# SparkFun_Analog_MEMS_Microphone_Breakout.net
KiCad netlist of a schematic drawn in EAGLE
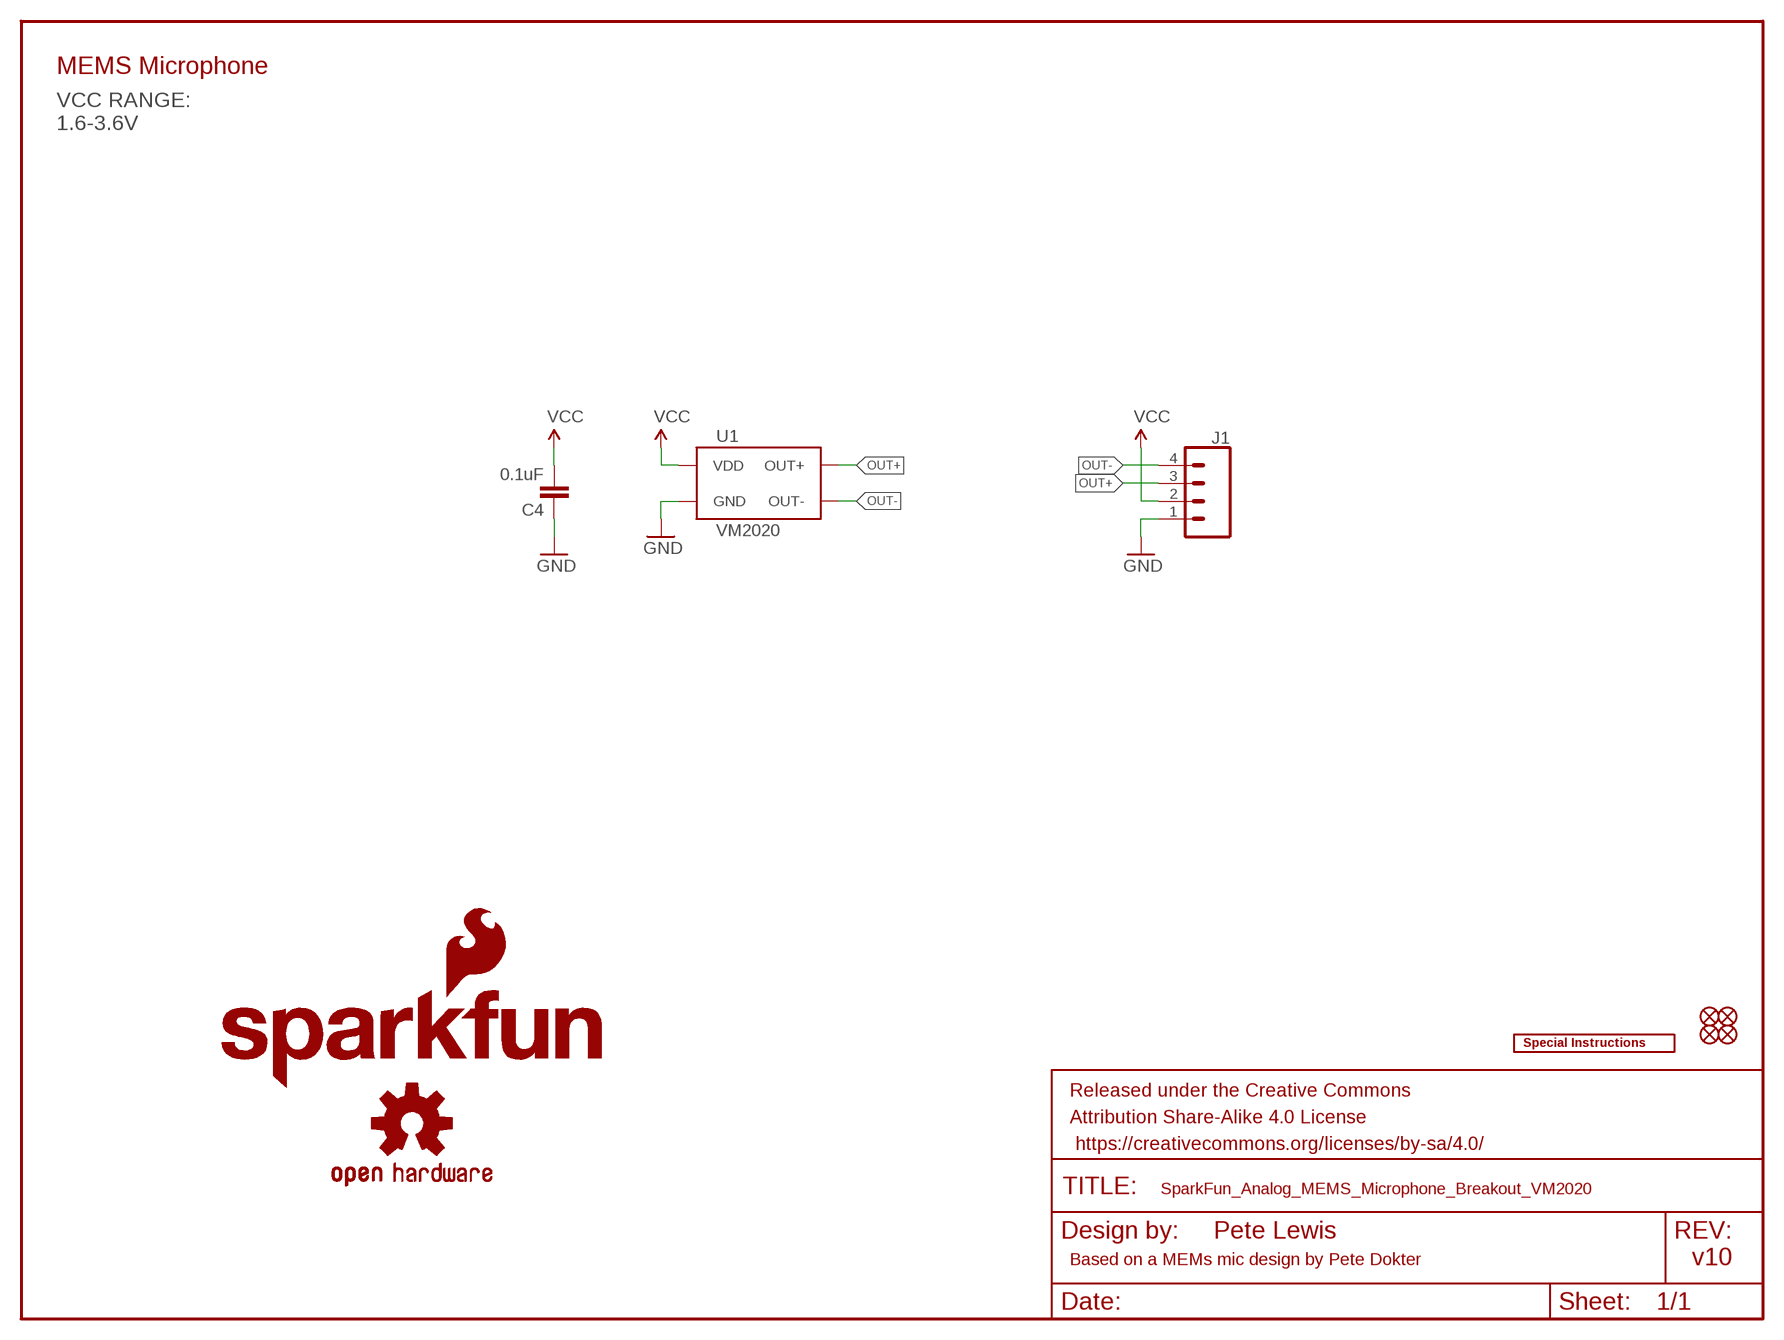
[diagram p0: schematic, sheet 1]

(export (version "E")
  (design (tool "Eeschema 10.0.6"))
  (components
    (comp (ref "C4")
      (value "0.1uF")
      (footprint "eagle-import:0603")
      (libsource (lib "eagle-import") (part "0.1UF-0603-25V-(+80/-20%)"))
    )
    (comp (ref "FD1")
      (value "FIDUCIALUFIDUCIAL")
      (footprint "eagle-import:FIDUCIAL-MICRO")
      (libsource (lib "eagle-import") (part "FIDUCIALUFIDUCIAL"))
    )
    (comp (ref "FD2")
      (value "FIDUCIALUFIDUCIAL")
      (footprint "eagle-import:FIDUCIAL-MICRO")
      (libsource (lib "eagle-import") (part "FIDUCIALUFIDUCIAL"))
    )
    (comp (ref "FD3")
      (value "FIDUCIALUFIDUCIAL")
      (footprint "eagle-import:FIDUCIAL-MICRO")
      (libsource (lib "eagle-import") (part "FIDUCIALUFIDUCIAL"))
    )
    (comp (ref "FD4")
      (value "FIDUCIALUFIDUCIAL")
      (footprint "eagle-import:FIDUCIAL-MICRO")
      (libsource (lib "eagle-import") (part "FIDUCIALUFIDUCIAL"))
    )
    (comp (ref "FRAME2")
      (value "FRAME-LETTER")
      (footprint "eagle-import:CREATIVE_COMMONS")
      (libsource (lib "eagle-import") (part "FRAME-LETTER"))
    )
    (comp (ref "J1")
      (value "CONN_041X04_NO_SILK")
      (footprint "eagle-import:1X04_NO_SILK")
      (libsource (lib "eagle-import") (part "CONN_041X04_NO_SILK"))
    )
    (comp (ref "LOGO1")
      (value "SFE_LOGO_FLAME.1_INCH")
      (footprint "eagle-import:SFE_LOGO_FLAME_.1")
      (libsource (lib "eagle-import") (part "SFE_LOGO_FLAME.1_INCH"))
    )
    (comp (ref "LOGO2")
      (value "OSHW-LOGOMINI")
      (footprint "eagle-import:OSHW-LOGO-MINI")
      (libsource (lib "eagle-import") (part "OSHW-LOGOMINI"))
    )
    (comp (ref "LOGO4")
      (value "SPECIAL_INSTRUCTIONS-ORDERING")
      (footprint "eagle-import:ORDERING_INSTRUCTIONS")
      (libsource (lib "eagle-import") (part "SPECIAL_INSTRUCTIONS-ORDERING"))
    )
    (comp (ref "U1")
      (value "VM2020")
      (footprint "eagle-import:VM2020")
      (libsource (lib "eagle-import") (part "VM2020"))
    )
  )
  (nets
    (net (code "1") (name "GND") (class "Default")
      (node (ref "C4") (pin "1") (pinfunction "1_1") (pintype "passive"))
      (node (ref "J1") (pin "1") (pinfunction "1_1") (pintype "passive"))
      (node (ref "U1") (pin "2") (pinfunction "GND_2") (pintype "power_in"))
      (node (ref "U1") (pin "3") (pinfunction "GND_3") (pintype "power_in"))
      (node (ref "U1") (pin "4") (pinfunction "GND_4") (pintype "power_in"))
      (node (ref "U1") (pin "5") (pinfunction "GND_5") (pintype "power_in"))
      (node (ref "U1") (pin "8") (pinfunction "GND_8") (pintype "power_in"))
    )
    (net (code "2") (name "OUT+") (class "Default")
      (node (ref "J1") (pin "3") (pinfunction "3_3") (pintype "passive"))
      (node (ref "U1") (pin "7") (pinfunction "OUT+_7") (pintype "output"))
    )
    (net (code "3") (name "OUT-") (class "Default")
      (node (ref "J1") (pin "4") (pinfunction "4_4") (pintype "passive"))
      (node (ref "U1") (pin "1") (pinfunction "OUT-_1") (pintype "input"))
    )
    (net (code "4") (name "VCC") (class "Default")
      (node (ref "C4") (pin "2") (pinfunction "2_2") (pintype "passive"))
      (node (ref "J1") (pin "2") (pinfunction "2_2") (pintype "passive"))
      (node (ref "U1") (pin "6") (pinfunction "VDD_6") (pintype "power_in"))
    )
  )
)
